# Memory.net
KiCad netlist of a schematic drawn in Altium Designer
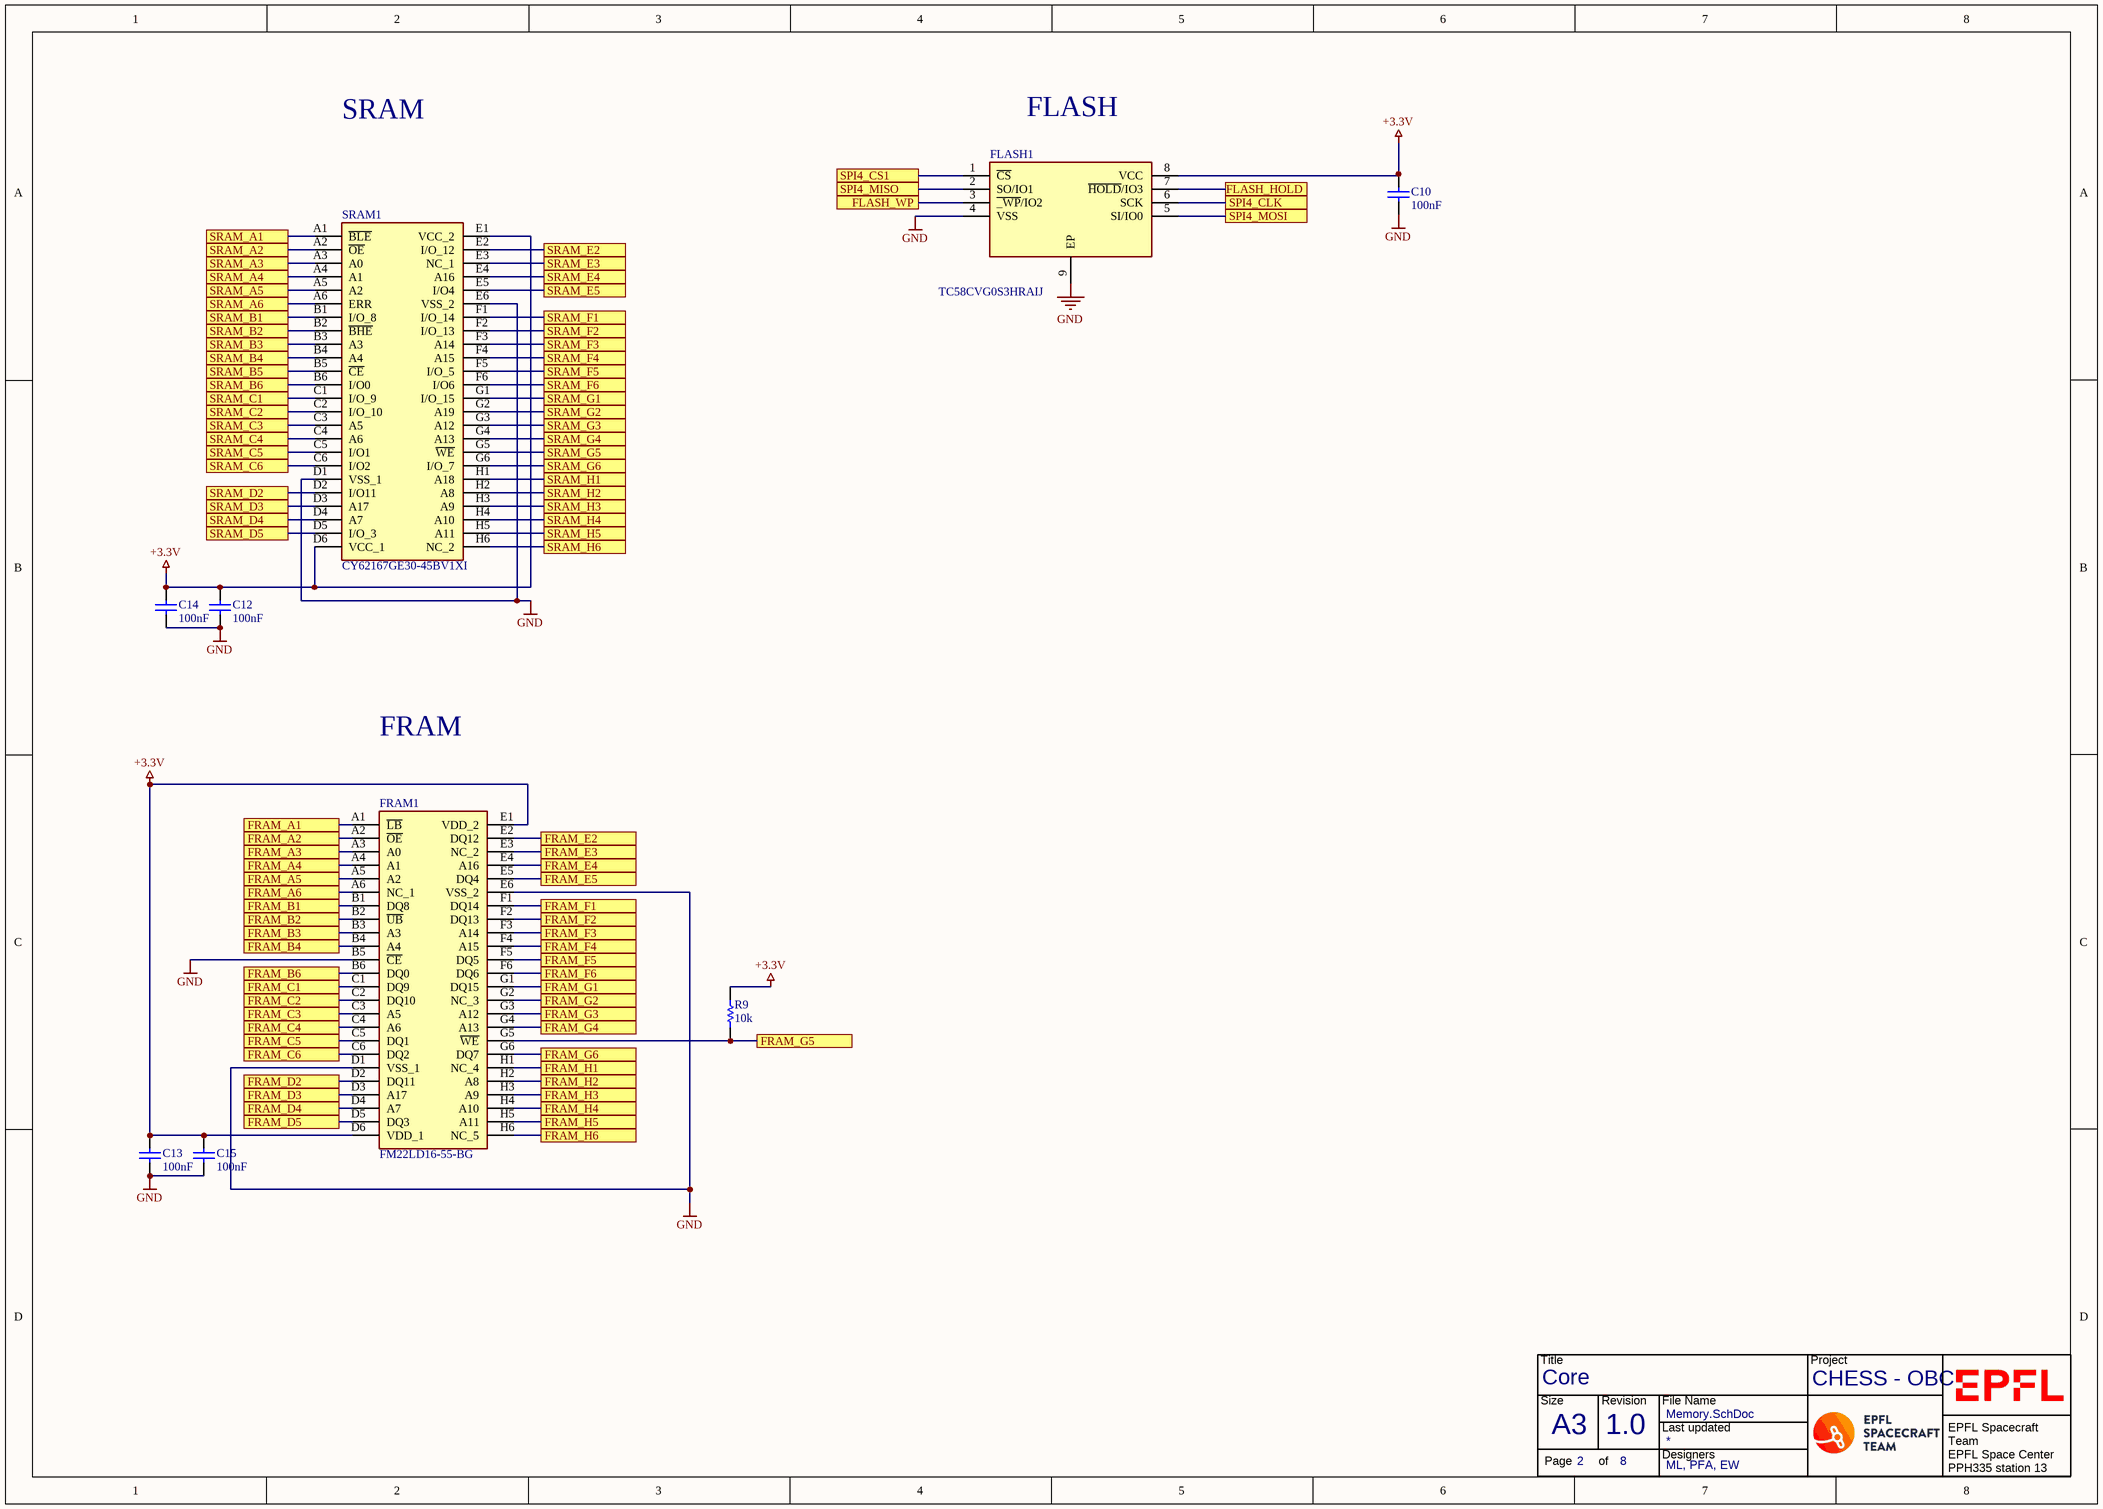
[diagram p0: Memory.SchDoc]

(export (version "E")
  (design (tool "Eeschema 10.0.6"))
  (components
    (comp (ref "C10")
      (value "100nF")
      (footprint "CAPC1005X60X30ML05T10")
      (fields (field (name "MANUFACTURER") "Kemet") (field (name "PART NUMBER") "C0402C104K8PACTU"))
      (libsource (lib "Altium Content Vault") (part "CAP"))
    )
    (comp (ref "C12")
      (value "100nF")
      (footprint "CAPC1005X60X30ML05T10")
      (fields (field (name "MANUFACTURER") "Kemet") (field (name "PART NUMBER") "C0402C104K8PACTU"))
      (libsource (lib "Altium Content Vault") (part "CAP"))
    )
    (comp (ref "C13")
      (value "100nF")
      (footprint "CAPC1005X60X30ML05T10")
      (fields (field (name "MANUFACTURER") "Kemet") (field (name "PART NUMBER") "C0402C104K8PACTU"))
      (libsource (lib "Altium Content Vault") (part "CAP"))
    )
    (comp (ref "C14")
      (value "100nF")
      (footprint "CAPC1005X60X30ML05T10")
      (fields (field (name "MANUFACTURER") "Kemet") (field (name "PART NUMBER") "C0402C104K8PACTU"))
      (libsource (lib "Altium Content Vault") (part "CAP"))
    )
    (comp (ref "C15")
      (value "100nF")
      (footprint "CAPC1005X60X30ML05T10")
      (fields (field (name "MANUFACTURER") "Kemet") (field (name "PART NUMBER") "C0402C104K8PACTU"))
      (libsource (lib "Altium Content Vault") (part "CAP"))
    )
    (comp (ref "FLASH1")
      (value "TC58CVG0S3HRAIJ")
      (footprint "SamacSys:SON127P800X600X80-9N-D")
      (description "Capacitor Polarised")
      (fields (field (name "MOUSER PART NUMBER") "757-TC58CVG0S3HRAIJ"))
      (libsource (lib "*") (part "TC58CVG0S3HRAIJ"))
    )
    (comp (ref "FRAM1")
      (value "FM22LD16-55-BG")
      (footprint "SamacSys:BGA48C75P6X8_600X800X120")
      (description "Integrated Circuit")
      (fields (field (name "MOUSER PART NUMBER") "877-FM22LD16-55-BG"))
      (libsource (lib "*") (part "FM22LD16-55-BG"))
    )
    (comp (ref "R9")
      (value "10k")
      (footprint "RESC1005X40X25LL05T10")
      (fields (field (name "PART NUMBER") "RC0402FR-0710KL") (field (name "MANUFACTURER") "Yageo / Phycomp"))
      (libsource (lib "Altium Content Vault") (part "RES"))
    )
    (comp (ref "SRAM1")
      (value "CY62167GE30-45BV1XI")
      (footprint "SamacSys:BGA48C75P6X8_600X800X100")
      (description "Integrated Circuit")
      (fields (field (name "MOUSER PART NUMBER") "727-CY62167GE30BV1XI"))
      (libsource (lib "*") (part "CY62167GE30-45BV1XI"))
    )
  )
  (nets
    (net (code "1") (name "+3.3V") (class "Default")
      (node (ref "C10") (pin "2") (pinfunction "2_2") (pintype "passive"))
      (node (ref "C12") (pin "2") (pinfunction "2_2") (pintype "passive"))
      (node (ref "C13") (pin "2") (pinfunction "2_2") (pintype "passive"))
      (node (ref "C14") (pin "2") (pinfunction "2_2") (pintype "passive"))
      (node (ref "C15") (pin "2") (pinfunction "2_2") (pintype "passive"))
      (node (ref "FLASH1") (pin "8") (pinfunction "VCC_8") (pintype "passive"))
      (node (ref "FRAM1") (pin "D6") (pinfunction "VDD_1_D6") (pintype "passive"))
      (node (ref "FRAM1") (pin "E1") (pinfunction "VDD_2_E1") (pintype "passive"))
      (node (ref "R9") (pin "2") (pinfunction "2_2") (pintype "passive"))
      (node (ref "SRAM1") (pin "D6") (pinfunction "VCC_1_D6") (pintype "passive"))
      (node (ref "SRAM1") (pin "E1") (pinfunction "VCC_2_E1") (pintype "passive"))
    )
    (net (code "2") (name "/FLASH_HOLD") (class "Default")
      (node (ref "FLASH1") (pin "7") (pinfunction "~{HOLD}/IO3_7") (pintype "passive"))
    )
    (net (code "3") (name "/FLASH_WP") (class "Default")
      (node (ref "FLASH1") (pin "3") (pinfunction "~{_WP}/IO2_3") (pintype "passive"))
    )
    (net (code "4") (name "/FRAM_A1") (class "Default")
      (node (ref "FRAM1") (pin "A1") (pinfunction "~{LB}_A1") (pintype "passive"))
    )
    (net (code "5") (name "/FRAM_A2") (class "Default")
      (node (ref "FRAM1") (pin "A2") (pinfunction "~{OE}_A2") (pintype "passive"))
    )
    (net (code "6") (name "/FRAM_A3") (class "Default")
      (node (ref "FRAM1") (pin "A3") (pinfunction "A0_A3") (pintype "passive"))
    )
    (net (code "7") (name "/FRAM_A4") (class "Default")
      (node (ref "FRAM1") (pin "A4") (pinfunction "A1_A4") (pintype "passive"))
    )
    (net (code "8") (name "/FRAM_A5") (class "Default")
      (node (ref "FRAM1") (pin "A5") (pinfunction "A2_A5") (pintype "passive"))
    )
    (net (code "9") (name "/FRAM_A6") (class "Default")
      (node (ref "FRAM1") (pin "A6") (pinfunction "NC_1_A6") (pintype "passive"))
    )
    (net (code "10") (name "/FRAM_B1") (class "Default")
      (node (ref "FRAM1") (pin "B1") (pinfunction "DQ8_B1") (pintype "passive"))
    )
    (net (code "11") (name "/FRAM_B2") (class "Default")
      (node (ref "FRAM1") (pin "B2") (pinfunction "~{UB}_B2") (pintype "passive"))
    )
    (net (code "12") (name "/FRAM_B3") (class "Default")
      (node (ref "FRAM1") (pin "B3") (pinfunction "A3_B3") (pintype "passive"))
    )
    (net (code "13") (name "/FRAM_B4") (class "Default")
      (node (ref "FRAM1") (pin "B4") (pinfunction "A4_B4") (pintype "passive"))
    )
    (net (code "14") (name "/FRAM_B6") (class "Default")
      (node (ref "FRAM1") (pin "B6") (pinfunction "DQ0_B6") (pintype "passive"))
    )
    (net (code "15") (name "/FRAM_C1") (class "Default")
      (node (ref "FRAM1") (pin "C1") (pinfunction "DQ9_C1") (pintype "passive"))
    )
    (net (code "16") (name "/FRAM_C2") (class "Default")
      (node (ref "FRAM1") (pin "C2") (pinfunction "DQ10_C2") (pintype "passive"))
    )
    (net (code "17") (name "/FRAM_C3") (class "Default")
      (node (ref "FRAM1") (pin "C3") (pinfunction "A5_C3") (pintype "passive"))
    )
    (net (code "18") (name "/FRAM_C4") (class "Default")
      (node (ref "FRAM1") (pin "C4") (pinfunction "A6_C4") (pintype "passive"))
    )
    (net (code "19") (name "/FRAM_C5") (class "Default")
      (node (ref "FRAM1") (pin "C5") (pinfunction "DQ1_C5") (pintype "passive"))
    )
    (net (code "20") (name "/FRAM_C6") (class "Default")
      (node (ref "FRAM1") (pin "C6") (pinfunction "DQ2_C6") (pintype "passive"))
    )
    (net (code "21") (name "/FRAM_D2") (class "Default")
      (node (ref "FRAM1") (pin "D2") (pinfunction "DQ11_D2") (pintype "passive"))
    )
    (net (code "22") (name "/FRAM_D3") (class "Default")
      (node (ref "FRAM1") (pin "D3") (pinfunction "A17_D3") (pintype "passive"))
    )
    (net (code "23") (name "/FRAM_D4") (class "Default")
      (node (ref "FRAM1") (pin "D4") (pinfunction "A7_D4") (pintype "passive"))
    )
    (net (code "24") (name "/FRAM_D5") (class "Default")
      (node (ref "FRAM1") (pin "D5") (pinfunction "DQ3_D5") (pintype "passive"))
    )
    (net (code "25") (name "/FRAM_E2") (class "Default")
      (node (ref "FRAM1") (pin "E2") (pinfunction "DQ12_E2") (pintype "passive"))
    )
    (net (code "26") (name "/FRAM_E3") (class "Default")
      (node (ref "FRAM1") (pin "E3") (pinfunction "NC_2_E3") (pintype "passive"))
    )
    (net (code "27") (name "/FRAM_E4") (class "Default")
      (node (ref "FRAM1") (pin "E4") (pinfunction "A16_E4") (pintype "passive"))
    )
    (net (code "28") (name "/FRAM_E5") (class "Default")
      (node (ref "FRAM1") (pin "E5") (pinfunction "DQ4_E5") (pintype "passive"))
    )
    (net (code "29") (name "/FRAM_F1") (class "Default")
      (node (ref "FRAM1") (pin "F1") (pinfunction "DQ14_F1") (pintype "passive"))
    )
    (net (code "30") (name "/FRAM_F2") (class "Default")
      (node (ref "FRAM1") (pin "F2") (pinfunction "DQ13_F2") (pintype "passive"))
    )
    (net (code "31") (name "/FRAM_F3") (class "Default")
      (node (ref "FRAM1") (pin "F3") (pinfunction "A14_F3") (pintype "passive"))
    )
    (net (code "32") (name "/FRAM_F4") (class "Default")
      (node (ref "FRAM1") (pin "F4") (pinfunction "A15_F4") (pintype "passive"))
    )
    (net (code "33") (name "/FRAM_F5") (class "Default")
      (node (ref "FRAM1") (pin "F5") (pinfunction "DQ5_F5") (pintype "passive"))
    )
    (net (code "34") (name "/FRAM_F6") (class "Default")
      (node (ref "FRAM1") (pin "F6") (pinfunction "DQ6_F6") (pintype "passive"))
    )
    (net (code "35") (name "/FRAM_G1") (class "Default")
      (node (ref "FRAM1") (pin "G1") (pinfunction "DQ15_G1") (pintype "passive"))
    )
    (net (code "36") (name "/FRAM_G2") (class "Default")
      (node (ref "FRAM1") (pin "G2") (pinfunction "NC_3_G2") (pintype "passive"))
    )
    (net (code "37") (name "/FRAM_G3") (class "Default")
      (node (ref "FRAM1") (pin "G3") (pinfunction "A12_G3") (pintype "passive"))
    )
    (net (code "38") (name "/FRAM_G4") (class "Default")
      (node (ref "FRAM1") (pin "G4") (pinfunction "A13_G4") (pintype "passive"))
    )
    (net (code "39") (name "/FRAM_G5") (class "Default")
      (node (ref "FRAM1") (pin "G5") (pinfunction "~{WE}_G5") (pintype "passive"))
      (node (ref "R9") (pin "1") (pinfunction "1_1") (pintype "passive"))
    )
    (net (code "40") (name "/FRAM_G6") (class "Default")
      (node (ref "FRAM1") (pin "G6") (pinfunction "DQ7_G6") (pintype "passive"))
    )
    (net (code "41") (name "/FRAM_H1") (class "Default")
      (node (ref "FRAM1") (pin "H1") (pinfunction "NC_4_H1") (pintype "passive"))
    )
    (net (code "42") (name "/FRAM_H2") (class "Default")
      (node (ref "FRAM1") (pin "H2") (pinfunction "A8_H2") (pintype "passive"))
    )
    (net (code "43") (name "/FRAM_H3") (class "Default")
      (node (ref "FRAM1") (pin "H3") (pinfunction "A9_H3") (pintype "passive"))
    )
    (net (code "44") (name "/FRAM_H4") (class "Default")
      (node (ref "FRAM1") (pin "H4") (pinfunction "A10_H4") (pintype "passive"))
    )
    (net (code "45") (name "/FRAM_H5") (class "Default")
      (node (ref "FRAM1") (pin "H5") (pinfunction "A11_H5") (pintype "passive"))
    )
    (net (code "46") (name "/FRAM_H6") (class "Default")
      (node (ref "FRAM1") (pin "H6") (pinfunction "NC_5_H6") (pintype "passive"))
    )
    (net (code "47") (name "/SPI4_CLK") (class "Default")
      (node (ref "FLASH1") (pin "6") (pinfunction "SCK_6") (pintype "passive"))
    )
    (net (code "48") (name "/SPI4_CS1") (class "Default")
      (node (ref "FLASH1") (pin "1") (pinfunction "~{CS}_1") (pintype "passive"))
    )
    (net (code "49") (name "/SPI4_MISO") (class "Default")
      (node (ref "FLASH1") (pin "2") (pinfunction "SO/IO1_2") (pintype "passive"))
    )
    (net (code "50") (name "/SPI4_MOSI") (class "Default")
      (node (ref "FLASH1") (pin "5") (pinfunction "SI/IO0_5") (pintype "passive"))
    )
    (net (code "51") (name "/SRAM_A1") (class "Default")
      (node (ref "SRAM1") (pin "A1") (pinfunction "~{BLE}_A1") (pintype "passive"))
    )
    (net (code "52") (name "/SRAM_A2") (class "Default")
      (node (ref "SRAM1") (pin "A2") (pinfunction "~{OE}_A2") (pintype "passive"))
    )
    (net (code "53") (name "/SRAM_A3") (class "Default")
      (node (ref "SRAM1") (pin "A3") (pinfunction "A0_A3") (pintype "passive"))
    )
    (net (code "54") (name "/SRAM_A4") (class "Default")
      (node (ref "SRAM1") (pin "A4") (pinfunction "A1_A4") (pintype "passive"))
    )
    (net (code "55") (name "/SRAM_A5") (class "Default")
      (node (ref "SRAM1") (pin "A5") (pinfunction "A2_A5") (pintype "passive"))
    )
    (net (code "56") (name "/SRAM_A6") (class "Default")
      (node (ref "SRAM1") (pin "A6") (pinfunction "ERR_A6") (pintype "passive"))
    )
    (net (code "57") (name "/SRAM_B1") (class "Default")
      (node (ref "SRAM1") (pin "B1") (pinfunction "I/O_8_B1") (pintype "passive"))
    )
    (net (code "58") (name "/SRAM_B2") (class "Default")
      (node (ref "SRAM1") (pin "B2") (pinfunction "~{BHE}_B2") (pintype "passive"))
    )
    (net (code "59") (name "/SRAM_B3") (class "Default")
      (node (ref "SRAM1") (pin "B3") (pinfunction "A3_B3") (pintype "passive"))
    )
    (net (code "60") (name "/SRAM_B4") (class "Default")
      (node (ref "SRAM1") (pin "B4") (pinfunction "A4_B4") (pintype "passive"))
    )
    (net (code "61") (name "/SRAM_B5") (class "Default")
      (node (ref "SRAM1") (pin "B5") (pinfunction "~{CE}_B5") (pintype "passive"))
    )
    (net (code "62") (name "/SRAM_B6") (class "Default")
      (node (ref "SRAM1") (pin "B6") (pinfunction "I/O0_B6") (pintype "passive"))
    )
    (net (code "63") (name "/SRAM_C1") (class "Default")
      (node (ref "SRAM1") (pin "C1") (pinfunction "I/O_9_C1") (pintype "passive"))
    )
    (net (code "64") (name "/SRAM_C2") (class "Default")
      (node (ref "SRAM1") (pin "C2") (pinfunction "I/O_10_C2") (pintype "passive"))
    )
    (net (code "65") (name "/SRAM_C3") (class "Default")
      (node (ref "SRAM1") (pin "C3") (pinfunction "A5_C3") (pintype "passive"))
    )
    (net (code "66") (name "/SRAM_C4") (class "Default")
      (node (ref "SRAM1") (pin "C4") (pinfunction "A6_C4") (pintype "passive"))
    )
    (net (code "67") (name "/SRAM_C5") (class "Default")
      (node (ref "SRAM1") (pin "C5") (pinfunction "I/O1_C5") (pintype "passive"))
    )
    (net (code "68") (name "/SRAM_C6") (class "Default")
      (node (ref "SRAM1") (pin "C6") (pinfunction "I/O2_C6") (pintype "passive"))
    )
    (net (code "69") (name "/SRAM_D2") (class "Default")
      (node (ref "SRAM1") (pin "D2") (pinfunction "I/O11_D2") (pintype "passive"))
    )
    (net (code "70") (name "/SRAM_D3") (class "Default")
      (node (ref "SRAM1") (pin "D3") (pinfunction "A17_D3") (pintype "passive"))
    )
    (net (code "71") (name "/SRAM_D4") (class "Default")
      (node (ref "SRAM1") (pin "D4") (pinfunction "A7_D4") (pintype "passive"))
    )
    (net (code "72") (name "/SRAM_D5") (class "Default")
      (node (ref "SRAM1") (pin "D5") (pinfunction "I/O_3_D5") (pintype "passive"))
    )
    (net (code "73") (name "/SRAM_E2") (class "Default")
      (node (ref "SRAM1") (pin "E2") (pinfunction "I/O_12_E2") (pintype "passive"))
    )
    (net (code "74") (name "/SRAM_E3") (class "Default")
      (node (ref "SRAM1") (pin "E3") (pinfunction "NC_1_E3") (pintype "passive"))
    )
    (net (code "75") (name "/SRAM_E4") (class "Default")
      (node (ref "SRAM1") (pin "E4") (pinfunction "A16_E4") (pintype "passive"))
    )
    (net (code "76") (name "/SRAM_E5") (class "Default")
      (node (ref "SRAM1") (pin "E5") (pinfunction "I/O4_E5") (pintype "passive"))
    )
    (net (code "77") (name "/SRAM_F1") (class "Default")
      (node (ref "SRAM1") (pin "F1") (pinfunction "I/O_14_F1") (pintype "passive"))
    )
    (net (code "78") (name "/SRAM_F2") (class "Default")
      (node (ref "SRAM1") (pin "F2") (pinfunction "I/O_13_F2") (pintype "passive"))
    )
    (net (code "79") (name "/SRAM_F3") (class "Default")
      (node (ref "SRAM1") (pin "F3") (pinfunction "A14_F3") (pintype "passive"))
    )
    (net (code "80") (name "/SRAM_F4") (class "Default")
      (node (ref "SRAM1") (pin "F4") (pinfunction "A15_F4") (pintype "passive"))
    )
    (net (code "81") (name "/SRAM_F5") (class "Default")
      (node (ref "SRAM1") (pin "F5") (pinfunction "I/O_5_F5") (pintype "passive"))
    )
    (net (code "82") (name "/SRAM_F6") (class "Default")
      (node (ref "SRAM1") (pin "F6") (pinfunction "I/O6_F6") (pintype "passive"))
    )
    (net (code "83") (name "/SRAM_G1") (class "Default")
      (node (ref "SRAM1") (pin "G1") (pinfunction "I/O_15_G1") (pintype "passive"))
    )
    (net (code "84") (name "/SRAM_G2") (class "Default")
      (node (ref "SRAM1") (pin "G2") (pinfunction "A19_G2") (pintype "passive"))
    )
    (net (code "85") (name "/SRAM_G3") (class "Default")
      (node (ref "SRAM1") (pin "G3") (pinfunction "A12_G3") (pintype "passive"))
    )
    (net (code "86") (name "/SRAM_G4") (class "Default")
      (node (ref "SRAM1") (pin "G4") (pinfunction "A13_G4") (pintype "passive"))
    )
    (net (code "87") (name "/SRAM_G5") (class "Default")
      (node (ref "SRAM1") (pin "G5") (pinfunction "~{WE}_G5") (pintype "passive"))
    )
    (net (code "88") (name "/SRAM_G6") (class "Default")
      (node (ref "SRAM1") (pin "G6") (pinfunction "I/O_7_G6") (pintype "passive"))
    )
    (net (code "89") (name "/SRAM_H1") (class "Default")
      (node (ref "SRAM1") (pin "H1") (pinfunction "A18_H1") (pintype "passive"))
    )
    (net (code "90") (name "/SRAM_H2") (class "Default")
      (node (ref "SRAM1") (pin "H2") (pinfunction "A8_H2") (pintype "passive"))
    )
    (net (code "91") (name "/SRAM_H3") (class "Default")
      (node (ref "SRAM1") (pin "H3") (pinfunction "A9_H3") (pintype "passive"))
    )
    (net (code "92") (name "/SRAM_H4") (class "Default")
      (node (ref "SRAM1") (pin "H4") (pinfunction "A10_H4") (pintype "passive"))
    )
    (net (code "93") (name "/SRAM_H5") (class "Default")
      (node (ref "SRAM1") (pin "H5") (pinfunction "A11_H5") (pintype "passive"))
    )
    (net (code "94") (name "/SRAM_H6") (class "Default")
      (node (ref "SRAM1") (pin "H6") (pinfunction "NC_2_H6") (pintype "passive"))
    )
    (net (code "95") (name "GND") (class "Default")
      (node (ref "C10") (pin "1") (pinfunction "1_1") (pintype "passive"))
      (node (ref "C12") (pin "1") (pinfunction "1_1") (pintype "passive"))
      (node (ref "C13") (pin "1") (pinfunction "1_1") (pintype "passive"))
      (node (ref "C14") (pin "1") (pinfunction "1_1") (pintype "passive"))
      (node (ref "C15") (pin "1") (pinfunction "1_1") (pintype "passive"))
      (node (ref "FLASH1") (pin "4") (pinfunction "VSS_4") (pintype "passive"))
      (node (ref "FLASH1") (pin "9") (pinfunction "EP_9") (pintype "passive"))
      (node (ref "FRAM1") (pin "B5") (pinfunction "~{CE}_B5") (pintype "passive"))
      (node (ref "FRAM1") (pin "D1") (pinfunction "VSS_1_D1") (pintype "passive"))
      (node (ref "FRAM1") (pin "E6") (pinfunction "VSS_2_E6") (pintype "passive"))
      (node (ref "SRAM1") (pin "D1") (pinfunction "VSS_1_D1") (pintype "passive"))
      (node (ref "SRAM1") (pin "E6") (pinfunction "VSS_2_E6") (pintype "passive"))
    )
  )
)
